# TB6560AHQ_stepper_driver.net
KiCad netlist of a schematic drawn in Altium Designer
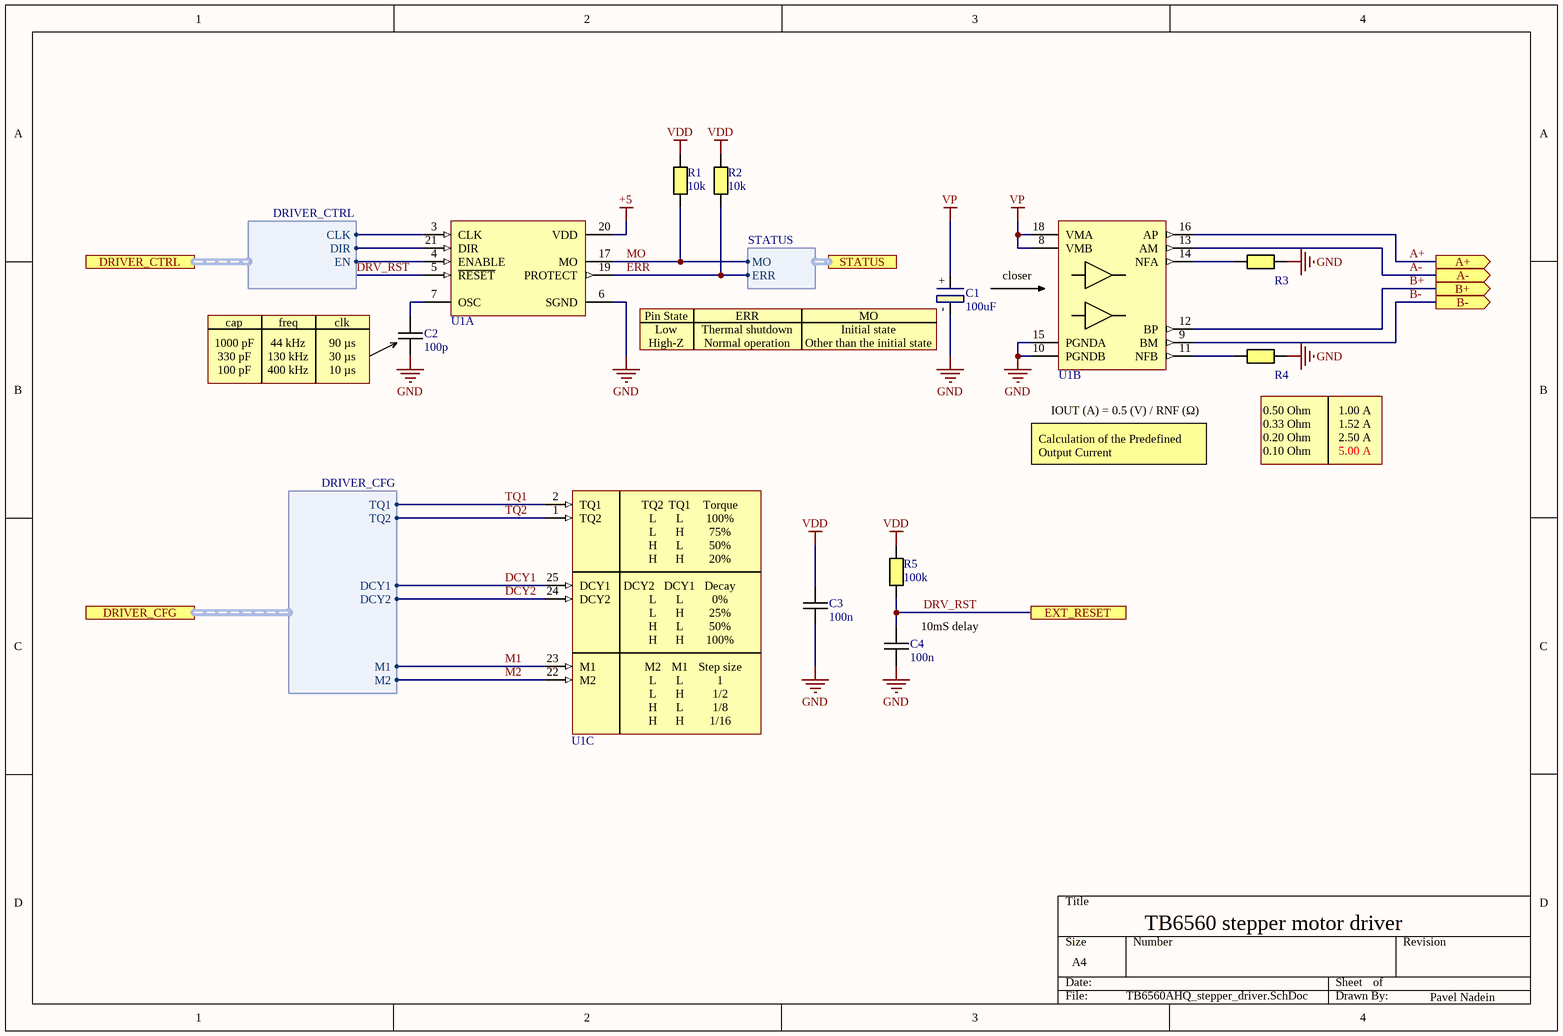
[diagram p0: TB6560AHQ_stepper_driver.SchDoc]

(export (version "E")
  (design (tool "Eeschema 10.0.6"))
  (components
    (comp (ref "C1")
      (value "100uF")
      (footprint "10x10.5 Capacitor")
      (description "Capacitor Electrolitic")
      (libsource (lib "Discrete_Passive_RCL") (part "Capacitor Electrolitic"))
    )
    (comp (ref "C2")
      (value "100p")
      (footprint "CAPC0603(1608)55_N")
      (description "Ceramic capacitor Medium density")
      (libsource (lib "Discrete_Passive_RCL") (part "Capacitor M"))
    )
    (comp (ref "C3")
      (value "100n")
      (footprint "CAPC0603(1608)55_N")
      (description "Ceramic capacitor Medium density")
      (libsource (lib "Discrete_Passive_RCL") (part "Capacitor M"))
    )
    (comp (ref "C4")
      (value "100n")
      (footprint "CAPC0603(1608)55_N")
      (description "Ceramic capacitor Medium density")
      (libsource (lib "Discrete_Passive_RCL") (part "Capacitor M"))
    )
    (comp (ref "R1")
      (value "10k")
      (footprint "RESC0603(1608)_N")
      (description "Resistor Medium Density")
      (libsource (lib "") (part "Resistor M_1"))
    )
    (comp (ref "R2")
      (value "10k")
      (footprint "RESC0603(1608)_N")
      (description "Resistor Medium Density")
      (libsource (lib "") (part "Resistor M_1"))
    )
    (comp (ref "R3")
      (value "TBD")
      (footprint "RESC2512(6432)_N")
      (description "Resistor Medium Density")
      (libsource (lib "Discrete_Passive_RCL") (part "Resistor M"))
    )
    (comp (ref "R4")
      (value "TBD")
      (footprint "RESC2512(6432)_N")
      (description "Resistor Medium Density")
      (libsource (lib "Discrete_Passive_RCL") (part "Resistor M"))
    )
    (comp (ref "R5")
      (value "100k")
      (footprint "RESC0603(1608)_N")
      (description "Resistor Medium Density")
      (libsource (lib "") (part "Resistor M_1"))
    )
    (comp (ref "U1")
      (value "STP DRIVER")
      (footprint "HZIP25_PCB")
      (libsource (lib "IntegrationCircuits") (part "TB6560AHQ"))
    )
  )
  (nets
    (net (code "4") (name "+5") (class "Default")
      (node (ref "U1") (pin "20") (pinfunction "VDD_20") (pintype "power_in"))
    )
    (net (code "5") (name "/A+") (class "Default")
      (node (ref "U1") (pin "16") (pinfunction "AP_16") (pintype "output"))
    )
    (net (code "6") (name "/A-") (class "Default")
      (node (ref "U1") (pin "13") (pinfunction "AM_13") (pintype "output"))
    )
    (net (code "7") (name "/B+") (class "Default")
      (node (ref "U1") (pin "12") (pinfunction "BP_12") (pintype "output"))
    )
    (net (code "8") (name "/B-") (class "Default")
      (node (ref "U1") (pin "9") (pinfunction "BM_9") (pintype "output"))
    )
    (net (code "9") (name "/CLK") (class "Default")
      (node (ref "U1") (pin "3") (pinfunction "CLK_3") (pintype "input"))
    )
    (net (code "10") (name "/DCY1") (class "Default")
      (node (ref "U1") (pin "25") (pinfunction "DCY1_25") (pintype "input"))
    )
    (net (code "11") (name "/DCY2") (class "Default")
      (node (ref "U1") (pin "24") (pinfunction "DCY2_24") (pintype "input"))
    )
    (net (code "12") (name "/DIR") (class "Default")
      (node (ref "U1") (pin "21") (pinfunction "DIR_21") (pintype "input"))
    )
    (net (code "13") (name "/DRV_RST") (class "Default")
      (node (ref "C4") (pin "1") (pinfunction "1_1") (pintype "passive"))
      (node (ref "R5") (pin "1") (pinfunction "1_1") (pintype "passive"))
      (node (ref "U1") (pin "5") (pinfunction "~{RESET}_5") (pintype "input"))
    )
    (net (code "14") (name "/EN") (class "Default")
      (node (ref "U1") (pin "4") (pinfunction "ENABLE_4") (pintype "input"))
    )
    (net (code "15") (name "/ERR") (class "Default")
      (node (ref "R2") (pin "1") (pinfunction "1_1") (pintype "passive"))
      (node (ref "U1") (pin "19") (pinfunction "PROTECT_19") (pintype "output"))
    )
    (net (code "16") (name "/M1") (class "Default")
      (node (ref "U1") (pin "23") (pinfunction "M1_23") (pintype "input"))
    )
    (net (code "17") (name "/M2") (class "Default")
      (node (ref "U1") (pin "22") (pinfunction "M2_22") (pintype "input"))
    )
    (net (code "18") (name "/MO") (class "Default")
      (node (ref "R1") (pin "1") (pinfunction "1_1") (pintype "passive"))
      (node (ref "U1") (pin "17") (pinfunction "MO_17") (pintype "open_collector"))
    )
    (net (code "19") (name "/TQ1") (class "Default")
      (node (ref "U1") (pin "2") (pinfunction "TQ1_2") (pintype "input"))
    )
    (net (code "20") (name "/TQ2") (class "Default")
      (node (ref "U1") (pin "1") (pinfunction "TQ2_1") (pintype "input"))
    )
    (net (code "24") (name "GND") (class "Default")
      (node (ref "C1") (pin "-") (pinfunction "-_-") (pintype "passive"))
      (node (ref "C2") (pin "2") (pinfunction "2_2") (pintype "passive"))
      (node (ref "C3") (pin "2") (pinfunction "2_2") (pintype "passive"))
      (node (ref "C4") (pin "2") (pinfunction "2_2") (pintype "passive"))
      (node (ref "R3") (pin "2") (pinfunction "2_2") (pintype "passive"))
      (node (ref "R4") (pin "2") (pinfunction "2_2") (pintype "passive"))
      (node (ref "U1") (pin "10") (pinfunction "PGNDB_10") (pintype "power_in"))
      (node (ref "U1") (pin "15") (pinfunction "PGNDA_15") (pintype "power_in"))
      (node (ref "U1") (pin "6") (pinfunction "SGND_6") (pintype "power_in"))
    )
    (net (code "25") (name "Net-(U1A-OSC)") (class "Default")
      (node (ref "C2") (pin "1") (pinfunction "1_1") (pintype "passive"))
      (node (ref "U1") (pin "7") (pinfunction "OSC_7") (pintype "passive"))
    )
    (net (code "26") (name "Net-(U1B-NFA)") (class "Default")
      (node (ref "R3") (pin "1") (pinfunction "1_1") (pintype "passive"))
      (node (ref "U1") (pin "14") (pinfunction "NFA_14") (pintype "output"))
    )
    (net (code "27") (name "Net-(U1B-NFB)") (class "Default")
      (node (ref "R4") (pin "1") (pinfunction "1_1") (pintype "passive"))
      (node (ref "U1") (pin "11") (pinfunction "NFB_11") (pintype "output"))
    )
    (net (code "28") (name "VDD") (class "Default")
      (node (ref "C3") (pin "1") (pinfunction "1_1") (pintype "passive"))
      (node (ref "R1") (pin "2") (pinfunction "2_2") (pintype "passive"))
      (node (ref "R2") (pin "2") (pinfunction "2_2") (pintype "passive"))
      (node (ref "R5") (pin "2") (pinfunction "2_2") (pintype "passive"))
    )
    (net (code "29") (name "VP") (class "Default")
      (node (ref "C1") (pin "+") (pinfunction "+_+") (pintype "passive"))
      (node (ref "U1") (pin "18") (pinfunction "VMA_18") (pintype "power_in"))
      (node (ref "U1") (pin "8") (pinfunction "VMB_8") (pintype "power_in"))
    )
  )
)
